# board.net
KiCad netlist of a schematic drawn in EAGLE
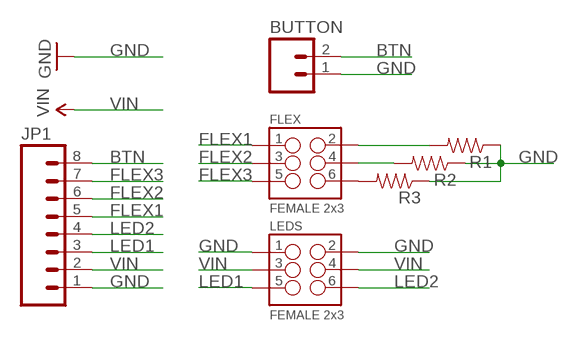
[diagram p0: schematic, sheet 1]

(export (version "E")
  (design (tool "Eeschema 10.0.6"))
  (components
    (comp (ref "BUTTON")
      (value "M02PTH")
      (footprint "eagle-import:1X02")
      (libsource (lib "eagle-import") (part "M02PTH"))
    )
    (comp (ref "FLEX")
      (value "FEMALE 2x3")
      (footprint "eagle-import:2X3")
      (libsource (lib "eagle-import") (part "M03X2FEMALE"))
    )
    (comp (ref "JP1")
      (value "M08NO_SILK_FEMALE_PTH")
      (footprint "eagle-import:1X08_NO_SILK")
      (libsource (lib "eagle-import") (part "M08NO_SILK_FEMALE_PTH"))
    )
    (comp (ref "LEDS")
      (value "FEMALE 2x3")
      (footprint "eagle-import:2X3")
      (libsource (lib "eagle-import") (part "M03X2FEMALE"))
    )
    (comp (ref "R1")
      (value "RESISTORPTH-1/4W")
      (footprint "eagle-import:AXIAL-0.4")
      (libsource (lib "eagle-import") (part "RESISTORPTH-1/4W"))
    )
    (comp (ref "R2")
      (value "RESISTORPTH-1/4W")
      (footprint "eagle-import:AXIAL-0.4")
      (libsource (lib "eagle-import") (part "RESISTORPTH-1/4W"))
    )
    (comp (ref "R3")
      (value "RESISTORPTH-1/4W")
      (footprint "eagle-import:AXIAL-0.4")
      (libsource (lib "eagle-import") (part "RESISTORPTH-1/4W"))
    )
  )
  (nets
    (net (code "1") (name "/BTN") (class "Default")
      (node (ref "BUTTON") (pin "2") (pinfunction "2_2") (pintype "passive"))
      (node (ref "JP1") (pin "8") (pinfunction "8_8") (pintype "passive"))
    )
    (net (code "2") (name "/FLEX1") (class "Default")
      (node (ref "FLEX") (pin "1") (pinfunction "1_1") (pintype "bidirectional"))
      (node (ref "JP1") (pin "5") (pinfunction "5_5") (pintype "passive"))
    )
    (net (code "3") (name "/FLEX2") (class "Default")
      (node (ref "FLEX") (pin "3") (pinfunction "3_3") (pintype "bidirectional"))
      (node (ref "JP1") (pin "6") (pinfunction "6_6") (pintype "passive"))
    )
    (net (code "4") (name "/FLEX3") (class "Default")
      (node (ref "FLEX") (pin "5") (pinfunction "5_5") (pintype "bidirectional"))
      (node (ref "JP1") (pin "7") (pinfunction "7_7") (pintype "passive"))
    )
    (net (code "5") (name "/LED1") (class "Default")
      (node (ref "JP1") (pin "3") (pinfunction "3_3") (pintype "passive"))
      (node (ref "LEDS") (pin "5") (pinfunction "5_5") (pintype "bidirectional"))
    )
    (net (code "6") (name "/LED2") (class "Default")
      (node (ref "JP1") (pin "4") (pinfunction "4_4") (pintype "passive"))
      (node (ref "LEDS") (pin "6") (pinfunction "6_6") (pintype "bidirectional"))
    )
    (net (code "7") (name "GND") (class "Default")
      (node (ref "BUTTON") (pin "1") (pinfunction "1_1") (pintype "passive"))
      (node (ref "JP1") (pin "1") (pinfunction "1_1") (pintype "passive"))
      (node (ref "LEDS") (pin "1") (pinfunction "1_1") (pintype "bidirectional"))
      (node (ref "LEDS") (pin "2") (pinfunction "2_2") (pintype "bidirectional"))
      (node (ref "R1") (pin "P$1") (pinfunction "1_P$1") (pintype "passive"))
      (node (ref "R2") (pin "P$1") (pinfunction "1_P$1") (pintype "passive"))
      (node (ref "R3") (pin "P$1") (pinfunction "1_P$1") (pintype "passive"))
    )
    (net (code "8") (name "Net-(R1-2)") (class "Default")
      (node (ref "FLEX") (pin "2") (pinfunction "2_2") (pintype "bidirectional"))
      (node (ref "R1") (pin "P$2") (pinfunction "2_P$2") (pintype "passive"))
    )
    (net (code "9") (name "Net-(R2-2)") (class "Default")
      (node (ref "FLEX") (pin "4") (pinfunction "4_4") (pintype "bidirectional"))
      (node (ref "R2") (pin "P$2") (pinfunction "2_P$2") (pintype "passive"))
    )
    (net (code "10") (name "Net-(R3-2)") (class "Default")
      (node (ref "FLEX") (pin "6") (pinfunction "6_6") (pintype "bidirectional"))
      (node (ref "R3") (pin "P$2") (pinfunction "2_P$2") (pintype "passive"))
    )
    (net (code "11") (name "VIN") (class "Default")
      (node (ref "JP1") (pin "2") (pinfunction "2_2") (pintype "passive"))
      (node (ref "LEDS") (pin "3") (pinfunction "3_3") (pintype "bidirectional"))
      (node (ref "LEDS") (pin "4") (pinfunction "4_4") (pintype "bidirectional"))
    )
  )
)
